# cgm_monitor.net
KiCad netlist of a schematic drawn in EAGLE
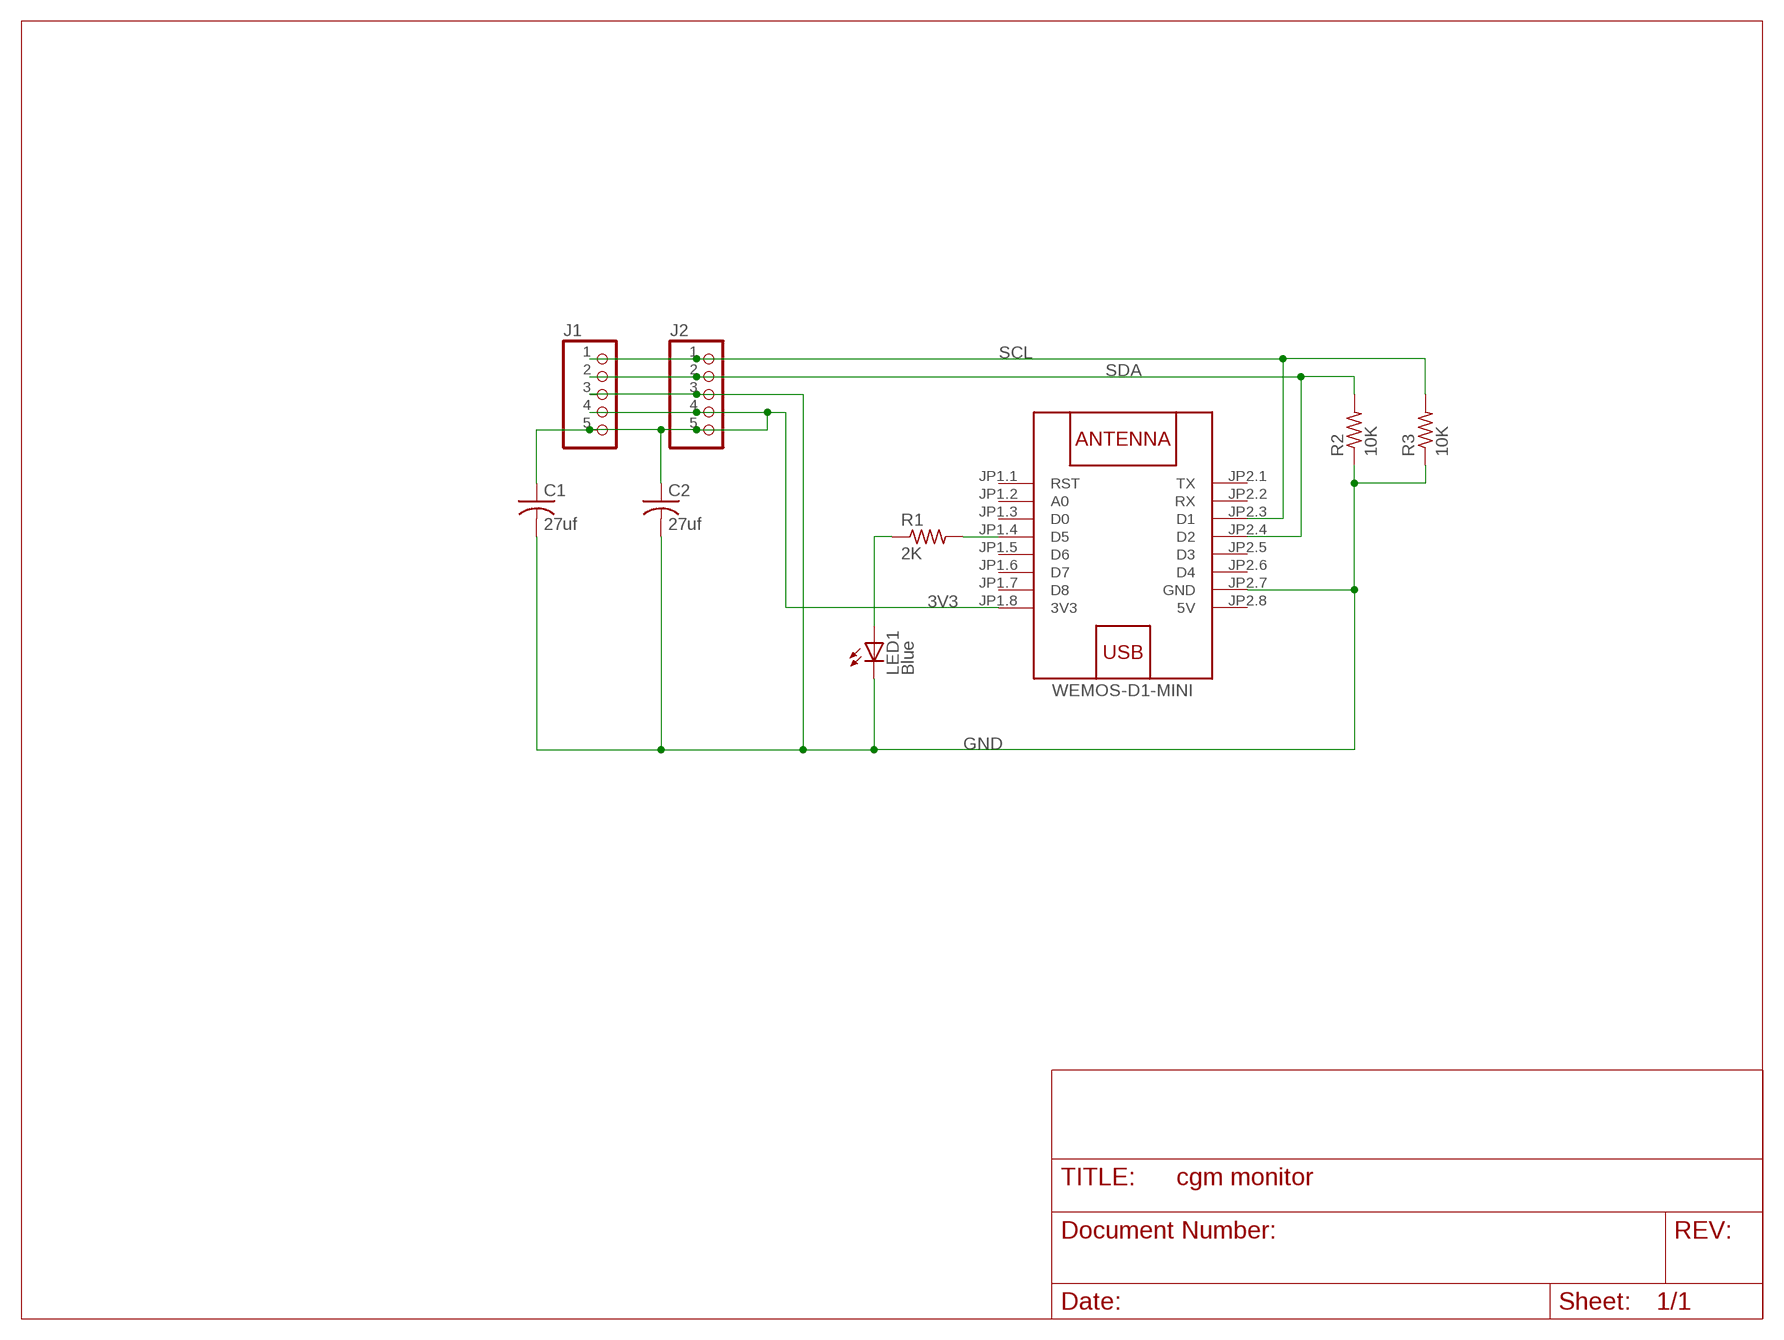
[diagram p0: schematic, sheet 1]

(export (version "E")
  (design (tool "Eeschema 10.0.6"))
  (components
    (comp (ref "C1")
      (value "27uf")
      (footprint "eagle-import:C050-050X075")
      (libsource (lib "eagle-import") (part "C-US050-050X075"))
    )
    (comp (ref "C2")
      (value "27uf")
      (footprint "eagle-import:C050-050X075")
      (libsource (lib "eagle-import") (part "C-US050-050X075"))
    )
    (comp (ref "J1")
      (value "PINHD-1X5")
      (footprint "eagle-import:1X05")
      (libsource (lib "eagle-import") (part "PINHD-1X5"))
    )
    (comp (ref "J2")
      (value "PINHD-1X5")
      (footprint "eagle-import:1X05")
      (libsource (lib "eagle-import") (part "PINHD-1X5"))
    )
    (comp (ref "LED1")
      (value "Blue")
      (footprint "eagle-import:LED5MM")
      (libsource (lib "eagle-import") (part "LED5MM"))
    )
    (comp (ref "R1")
      (value "2K")
      (footprint "eagle-import:0207_9")
      (libsource (lib "eagle-import") (part "R-US_0207/9"))
    )
    (comp (ref "R2")
      (value "10K")
      (footprint "eagle-import:0207_9")
      (libsource (lib "eagle-import") (part "R-US_0207/9"))
    )
    (comp (ref "R3")
      (value "10K")
      (footprint "eagle-import:0207_9")
      (libsource (lib "eagle-import") (part "R-US_0207/9"))
    )
    (comp (ref "W1")
      (value "WEMOS-D1-MINI")
      (footprint "eagle-import:WEMOS-D1-MINI")
      (libsource (lib "eagle-import") (part "WEMOS-D1-MINI"))
    )
  )
  (nets
    (net (code "1") (name "/3V3") (class "Default")
      (node (ref "C1") (pin "1") (pinfunction "1_1") (pintype "passive"))
      (node (ref "C2") (pin "1") (pinfunction "1_1") (pintype "passive"))
      (node (ref "J1") (pin "4") (pinfunction "4_4") (pintype "passive"))
      (node (ref "J1") (pin "5") (pinfunction "5_5") (pintype "passive"))
      (node (ref "J2") (pin "4") (pinfunction "4_4") (pintype "passive"))
      (node (ref "J2") (pin "5") (pinfunction "5_5") (pintype "passive"))
      (node (ref "W1") (pin "JP1.8") (pinfunction "3V3_JP1.8") (pintype "power_in"))
    )
    (net (code "2") (name "/5V") (class "Default")
      (node (ref "W1") (pin "JP2.8") (pinfunction "5V_JP2.8") (pintype "power_in"))
    )
    (net (code "3") (name "/GND") (class "Default")
      (node (ref "C1") (pin "2") (pinfunction "2_2") (pintype "passive"))
      (node (ref "C2") (pin "2") (pinfunction "2_2") (pintype "passive"))
      (node (ref "J1") (pin "3") (pinfunction "3_3") (pintype "passive"))
      (node (ref "J2") (pin "3") (pinfunction "3_3") (pintype "passive"))
      (node (ref "LED1") (pin "K") (pinfunction "C_K") (pintype "passive"))
      (node (ref "R2") (pin "1") (pinfunction "1_1") (pintype "passive"))
      (node (ref "R3") (pin "1") (pinfunction "1_1") (pintype "passive"))
      (node (ref "W1") (pin "JP2.7") (pinfunction "GND_JP2.7") (pintype "power_in"))
    )
    (net (code "4") (name "/SCL") (class "Default")
      (node (ref "J1") (pin "1") (pinfunction "1_1") (pintype "passive"))
      (node (ref "J2") (pin "1") (pinfunction "1_1") (pintype "passive"))
      (node (ref "R3") (pin "2") (pinfunction "2_2") (pintype "passive"))
      (node (ref "W1") (pin "JP2.3") (pinfunction "D1_JP2.3") (pintype "bidirectional"))
    )
    (net (code "5") (name "/SDA") (class "Default")
      (node (ref "J1") (pin "2") (pinfunction "2_2") (pintype "passive"))
      (node (ref "J2") (pin "2") (pinfunction "2_2") (pintype "passive"))
      (node (ref "R2") (pin "2") (pinfunction "2_2") (pintype "passive"))
      (node (ref "W1") (pin "JP2.4") (pinfunction "D2_JP2.4") (pintype "bidirectional"))
    )
    (net (code "6") (name "Net-(LED1-PadA)") (class "Default")
      (node (ref "LED1") (pin "A") (pinfunction "A_A") (pintype "passive"))
      (node (ref "R1") (pin "1") (pinfunction "1_1") (pintype "passive"))
    )
    (net (code "7") (name "Net-(W1-D5)") (class "Default")
      (node (ref "R1") (pin "2") (pinfunction "2_2") (pintype "passive"))
      (node (ref "W1") (pin "JP1.4") (pinfunction "D5_JP1.4") (pintype "bidirectional"))
    )
    (net (code "8") (name "unconnected-(W1-A0-PadJP1.2)") (class "Default")
      (node (ref "W1") (pin "JP1.2") (pinfunction "A0_JP1.2") (pintype "bidirectional"))
    )
    (net (code "9") (name "unconnected-(W1-D0-PadJP1.3)") (class "Default")
      (node (ref "W1") (pin "JP1.3") (pinfunction "D0_JP1.3") (pintype "bidirectional"))
    )
    (net (code "10") (name "unconnected-(W1-D3-PadJP2.5)") (class "Default")
      (node (ref "W1") (pin "JP2.5") (pinfunction "D3_JP2.5") (pintype "bidirectional"))
    )
    (net (code "11") (name "unconnected-(W1-D4-PadJP2.6)") (class "Default")
      (node (ref "W1") (pin "JP2.6") (pinfunction "D4_JP2.6") (pintype "bidirectional"))
    )
    (net (code "12") (name "unconnected-(W1-D6-PadJP1.5)") (class "Default")
      (node (ref "W1") (pin "JP1.5") (pinfunction "D6_JP1.5") (pintype "bidirectional"))
    )
    (net (code "13") (name "unconnected-(W1-D7-PadJP1.6)") (class "Default")
      (node (ref "W1") (pin "JP1.6") (pinfunction "D7_JP1.6") (pintype "bidirectional"))
    )
    (net (code "14") (name "unconnected-(W1-D8-PadJP1.7)") (class "Default")
      (node (ref "W1") (pin "JP1.7") (pinfunction "D8_JP1.7") (pintype "bidirectional"))
    )
    (net (code "15") (name "unconnected-(W1-RST-PadJP1.1)") (class "Default")
      (node (ref "W1") (pin "JP1.1") (pinfunction "RST_JP1.1") (pintype "bidirectional"))
    )
    (net (code "16") (name "unconnected-(W1-RX-PadJP2.2)") (class "Default")
      (node (ref "W1") (pin "JP2.2") (pinfunction "RX_JP2.2") (pintype "bidirectional"))
    )
    (net (code "17") (name "unconnected-(W1-TX-PadJP2.1)") (class "Default")
      (node (ref "W1") (pin "JP2.1") (pinfunction "TX_JP2.1") (pintype "bidirectional"))
    )
  )
)
